# Sheet1.net
KiCad netlist of a schematic drawn in Altium Designer
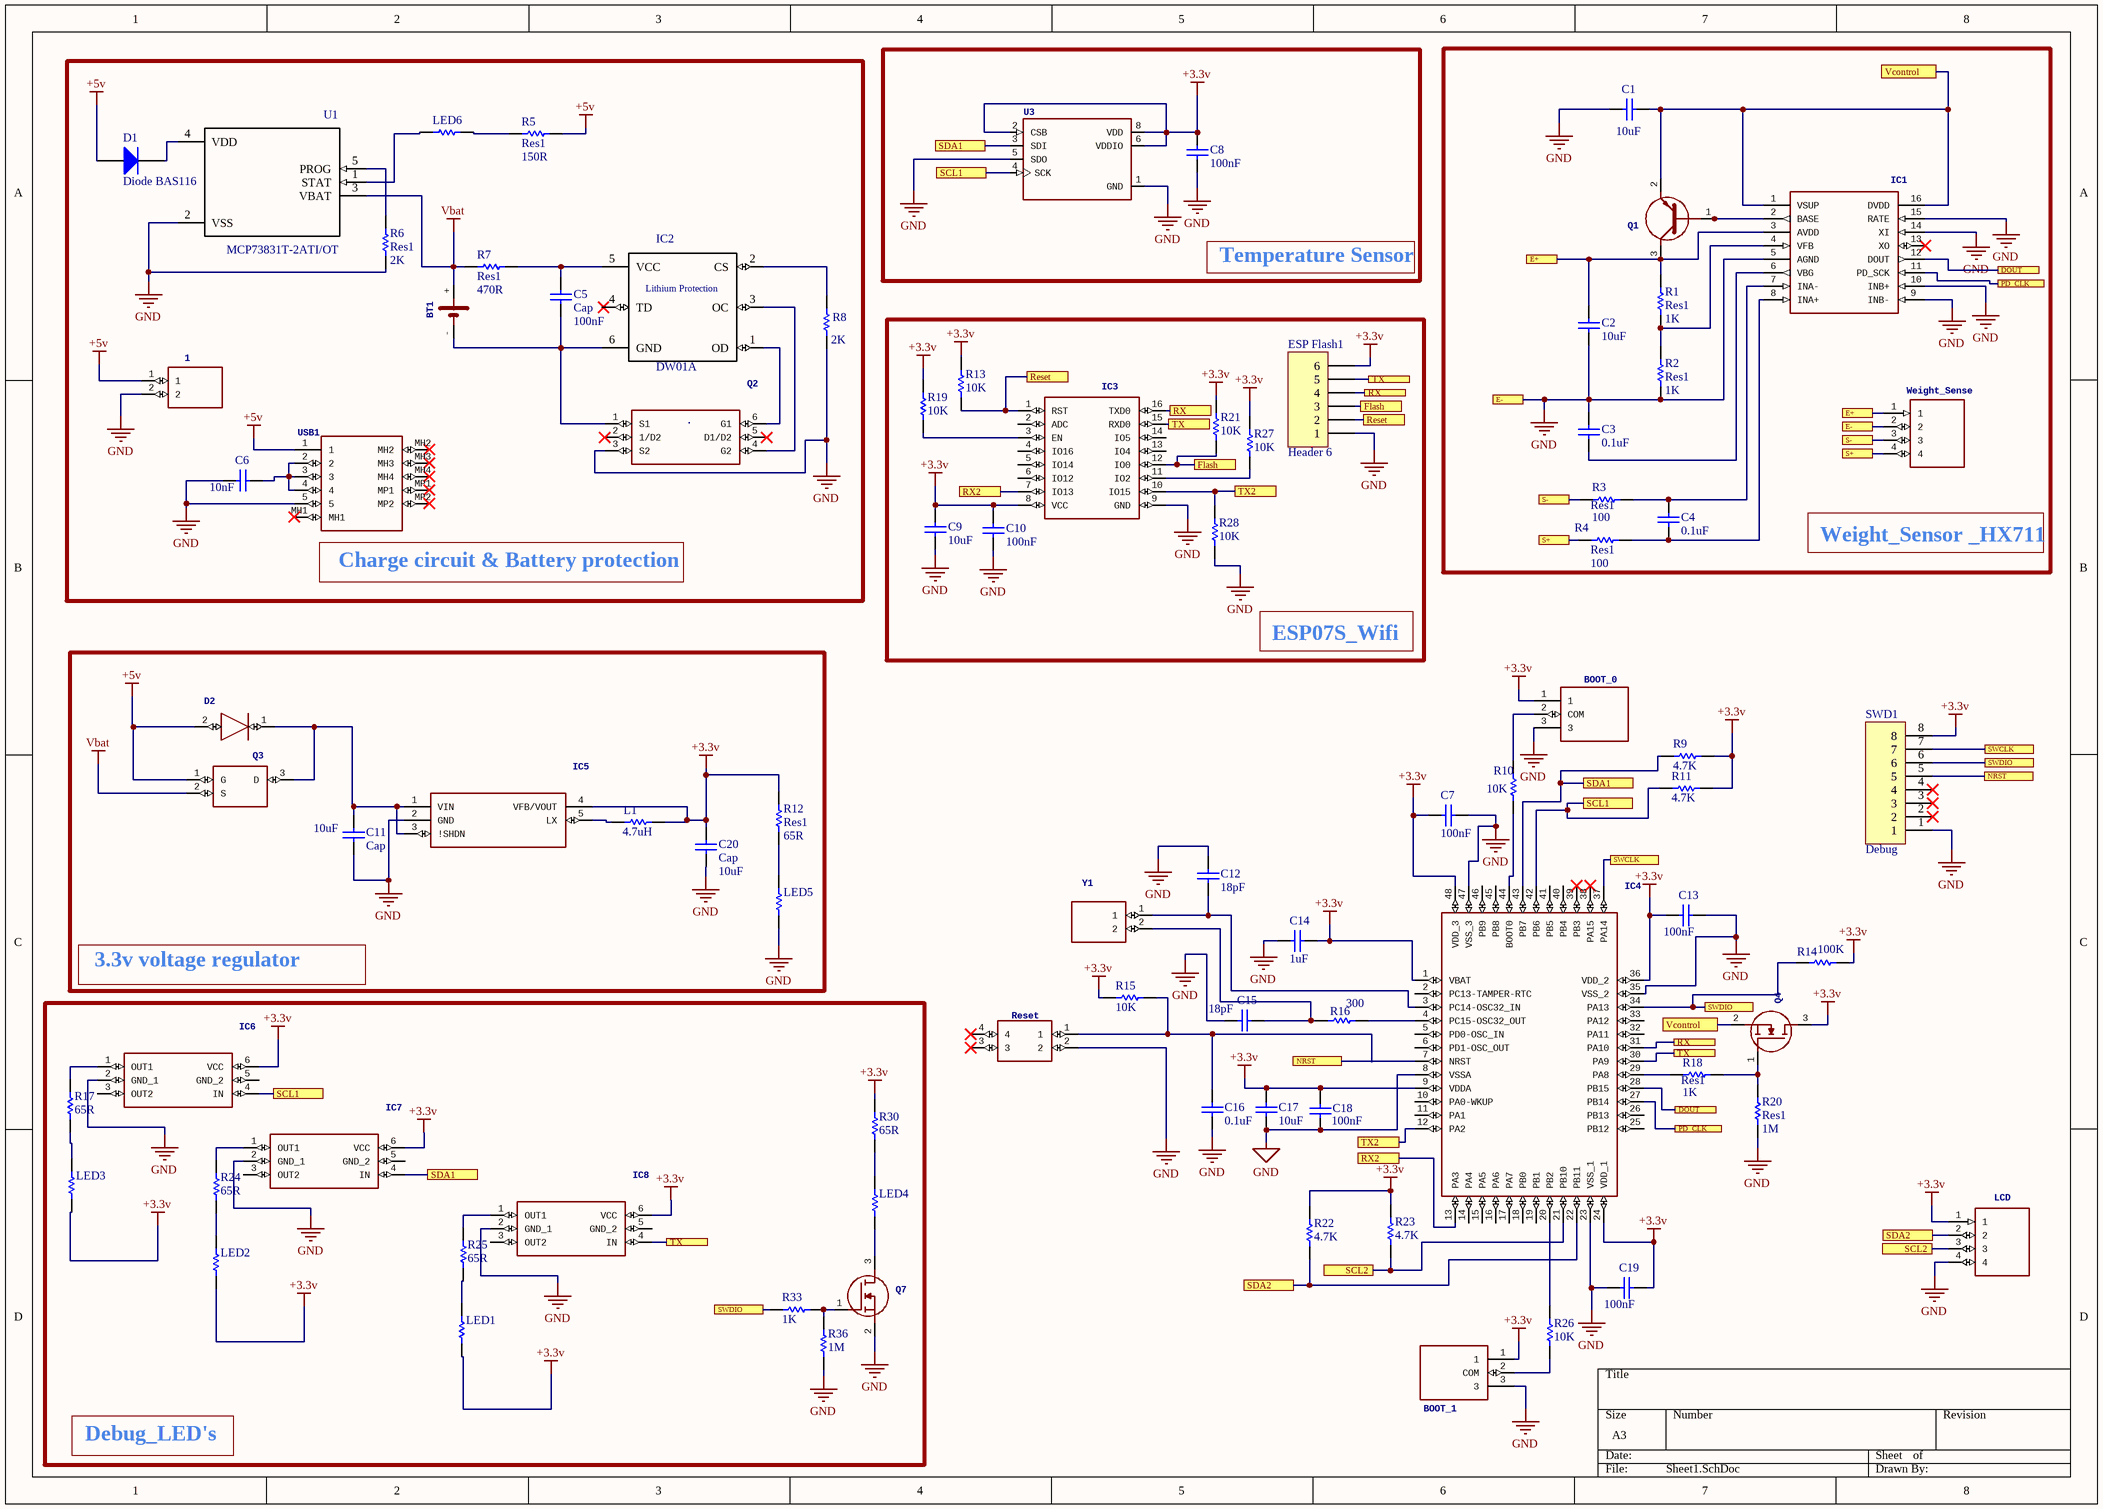
[diagram p0: Sheet1.SchDoc]

(export (version "E")
  (design (tool "Eeschema 10.0.6"))
  (components
    (comp (ref "1")
      (value "P=3.81mm Screw terminal   Source:  Datasheet")
      (footprint "SHDR2W80P0X381_1X2_802X740X880")
      (fields (field (name "MANUFACTURER_PART_NUMBER") "DB125-3.81-2P"))
      (libsource (lib "DB125-3") (part "DB125-3.81-2P"))
    )
    (comp (ref "BOOT_0")
      (value "Slide Switch   Source:  Datasheet")
      (footprint "3PIN_SLIDE_SWITCH")
      (fields
        (field (name "MANUFACTURER_PART_NUMBER") "EG1218")
        (field (name "MOUSER_PART_NUMBER") "612-EG1218")
      )
      (libsource (lib "EG1218") (part "EG1218"))
    )
    (comp (ref "BOOT_1")
      (value "Slide Switch   Source:  Datasheet")
      (footprint "3PIN_SLIDE_SWITCH")
      (fields
        (field (name "MANUFACTURER_PART_NUMBER") "EG1218")
        (field (name "MOUSER_PART_NUMBER") "612-EG1218")
      )
      (libsource (lib "EG1218") (part "EG1218"))
    )
    (comp (ref "BT1")
      (value "Lithium-Ion Battery Holder, 1 Cell, Plastic UL 94V-O, SMT Check prices")
      (footprint "BAT_1042")
      (fields (field (name "MF") "Keystone Electronics Corp.") (field (name "MP") "1042"))
      (libsource (lib "1042") (part "1042"))
    )
    (comp (ref "C1")
      (value "10uF")
      (footprint "C1206")
      (description "Capacitor (Semiconductor SIM Model)")
      (fields (field (name "Comment") "Cap Semi") (field (name "PUBLISHER") "Altium Limited"))
      (libsource (lib "Miscellaneous Devices") (part "Cap Semi"))
    )
    (comp (ref "C2")
      (value "10uF")
      (footprint "C1206")
      (description "Capacitor (Semiconductor SIM Model)")
      (fields (field (name "Comment") "Cap Semi") (field (name "PUBLISHER") "Altium Limited"))
      (libsource (lib "Miscellaneous Devices") (part "Cap Semi"))
    )
    (comp (ref "C3")
      (value "0.1uF")
      (footprint "C1206")
      (description "Capacitor (Semiconductor SIM Model)")
      (fields (field (name "Comment") "Cap Semi") (field (name "PUBLISHER") "Altium Limited"))
      (libsource (lib "Miscellaneous Devices") (part "Cap Semi"))
    )
    (comp (ref "C4")
      (value "0.1uF")
      (footprint "C1206")
      (description "Capacitor (Semiconductor SIM Model)")
      (fields (field (name "Comment") "Cap Semi") (field (name "PUBLISHER") "Altium Limited"))
      (libsource (lib "Miscellaneous Devices") (part "Cap Semi"))
    )
    (comp (ref "C5")
      (value "Cap")
      (footprint "C1206")
      (description "Capacitor")
      (fields (field (name "ALTIUM_VALUE") "100nF") (field (name "PUBLISHER") "Altium Limited"))
      (libsource (lib "Miscellaneous Devices") (part "Cap"))
    )
    (comp (ref "C6")
      (value "10nF")
      (footprint "C1206")
      (description "Capacitor")
      (fields (field (name "PUBLISHER") "Altium Limited"))
      (libsource (lib "Miscellaneous Devices") (part "Cap"))
    )
    (comp (ref "C7")
      (value "100nF")
      (footprint "C1206")
      (description "Capacitor")
      (fields (field (name "PUBLISHER") "Altium Limited"))
      (libsource (lib "Miscellaneous Devices") (part "Cap"))
    )
    (comp (ref "C8")
      (value "100nF")
      (footprint "C1206")
      (description "Capacitor")
      (fields (field (name "PUBLISHER") "Altium Limited"))
      (libsource (lib "Miscellaneous Devices") (part "Cap"))
    )
    (comp (ref "C9")
      (value "10uF")
      (footprint "C1206")
      (description "Capacitor")
      (fields (field (name "PUBLISHER") "Altium Limited"))
      (libsource (lib "Miscellaneous Devices") (part "Cap"))
    )
    (comp (ref "C10")
      (value "100nF")
      (footprint "C1206")
      (description "Capacitor")
      (fields (field (name "PUBLISHER") "Altium Limited"))
      (libsource (lib "Miscellaneous Devices") (part "Cap"))
    )
    (comp (ref "C11")
      (value "Cap")
      (footprint "C1206")
      (description "Capacitor")
      (fields (field (name "ALTIUM_VALUE") "10uF") (field (name "PUBLISHER") "Altium Limited"))
      (libsource (lib "Miscellaneous Devices") (part "Cap"))
    )
    (comp (ref "C12")
      (value "18pF")
      (footprint "C1206")
      (description "Capacitor")
      (fields (field (name "PUBLISHER") "Altium Limited"))
      (libsource (lib "Miscellaneous Devices") (part "Cap"))
    )
    (comp (ref "C13")
      (value "100nF")
      (footprint "C1206")
      (description "Capacitor")
      (fields (field (name "PUBLISHER") "Altium Limited"))
      (libsource (lib "Miscellaneous Devices") (part "Cap"))
    )
    (comp (ref "C14")
      (value "1uF")
      (footprint "C1206")
      (description "Capacitor")
      (fields (field (name "PUBLISHER") "Altium Limited"))
      (libsource (lib "Miscellaneous Devices") (part "Cap"))
    )
    (comp (ref "C15")
      (value "18pF")
      (footprint "C1206")
      (description "Capacitor")
      (fields (field (name "PUBLISHER") "Altium Limited"))
      (libsource (lib "Miscellaneous Devices") (part "Cap"))
    )
    (comp (ref "C16")
      (value "0.1uF")
      (footprint "C1206")
      (description "Capacitor")
      (fields (field (name "PUBLISHER") "Altium Limited"))
      (libsource (lib "Miscellaneous Devices") (part "Cap"))
    )
    (comp (ref "C17")
      (value "10uF")
      (footprint "C1206")
      (description "Capacitor")
      (fields (field (name "PUBLISHER") "Altium Limited"))
      (libsource (lib "Miscellaneous Devices") (part "Cap"))
    )
    (comp (ref "C18")
      (value "100nF")
      (footprint "C1206")
      (description "Capacitor")
      (fields (field (name "PUBLISHER") "Altium Limited"))
      (libsource (lib "Miscellaneous Devices") (part "Cap"))
    )
    (comp (ref "C19")
      (value "100nF")
      (footprint "C1206")
      (description "Capacitor")
      (fields (field (name "PUBLISHER") "Altium Limited"))
      (libsource (lib "Miscellaneous Devices") (part "Cap"))
    )
    (comp (ref "C20")
      (value "Cap")
      (footprint "C1206")
      (description "Capacitor")
      (fields (field (name "ALTIUM_VALUE") "10uF") (field (name "PUBLISHER") "Altium Limited"))
      (libsource (lib "Miscellaneous Devices") (part "Cap"))
    )
    (comp (ref "D1")
      (value "Diode BAS116")
      (footprint "SOT-23_N")
      (description "Silicon Low Leakage Diode")
      (fields (field (name "PUBLISHER") "Altium Limited"))
      (libsource (lib "Miscellaneous Devices") (part "Diode BAS116"))
    )
    (comp (ref "D2")
      (value "Diode, NXP, PMEG3010ER NXP PMEG3010ER, SMT Schottky Diode, 30V 1A, 2-Pin SOD-123   Source:  Datasheet")
      (footprint "SODFL3517X110N")
      (fields (field (name "MANUFACTURER_PART_NUMBER") "PMEG3010ER"))
      (libsource (lib "PMEG3010ER") (part "PMEG3010ER"))
    )
    (comp (ref "ESP Flash1")
      (value "Header 6")
      (footprint "HDR1X6")
      (description "Header, 6-Pin")
      (fields (field (name "PUBLISHER") "Altium Limited"))
      (libsource (lib "Miscellaneous Connectors") (part "Header 6"))
    )
    (comp (ref "IC1")
      (value "24-Bit Analog-to-Digital Converter (ADC) for Weigh Scales   Source:  Datasheet")
      (footprint "SOIC127P600X160-16N")
      (fields (field (name "MANUFACTURER_PART_NUMBER") "HX711"))
      (libsource (lib "HX711") (part "HX711"))
    )
    (comp (ref "IC2")
      (value "DW01A")
      (footprint "*SOT23-6")
      (description "One Cell Lithium-ion/Polymer Battery Protection IC")
      (fields (field (name "MF") "Fortune Semiconductor"))
      (libsource (lib "DW01A") (part "DW01A"))
    )
    (comp (ref "IC3")
      (value "RF SOLUTIONS - ESP-12S - WIFI MODULE, 2.484GHZ, 9 I/O PORT   Source:  Datasheet")
      (footprint "ESP12S")
      (fields
        (field (name "MANUFACTURER_PART_NUMBER") "ESP-12S")
        (field (name "MOUSER_PART_NUMBER") "223-ESP-12S")
        (field (name "RS_PART_NUMBER") "1697593")
      )
      (libsource (lib "ESP-12S") (part "ESP-12S"))
    )
    (comp (ref "IC4")
      (value "STM32F103C8T6, 32 bit ARM Cortex M3 Microcontroller 72MHz 64kb Flash, 20kb RAM, USB I2C SPI 48-Pin LQFP   Source:  Datasheet")
      (footprint "QFP50P900X900X160-48N")
      (fields
        (field (name "MANUFACTURER_PART_NUMBER") "STM32F103C8T6")
        (field (name "MOUSER_PART_NUMBER") "511-STM32F103C8T6")
      )
      (libsource (lib "STM32F103C8T6") (part "STM32F103C8T6"))
    )
    (comp (ref "IC5")
      (value "Sw. Reg. PWM/PFM 2MHz 500mA 3.3V TSOT5   Source:  Datasheet")
      (footprint "SOT95P280X110-5N")
      (fields
        (field (name "MANUFACTURER_PART_NUMBER") "MCP1603T-330I/OS")
        (field (name "MOUSER_PART_NUMBER") "579-MCP1603T-330I/OS")
        (field (name "RS_PART_NUMBER") "7386235P")
      )
      (libsource (lib "MCP1603T-330I_OS") (part "MCP1603T-330I_OS"))
    )
    (comp (ref "IC6")
      (value "MAXIM INTEGRATED PRODUCTS - MAX2472EUT+T - VIDEO BUFFER AMP, SOT-23-6   Source:  Datasheet")
      (footprint "SOT95P280X145-6N")
      (fields
        (field (name "MANUFACTURER_PART_NUMBER") "MAX2472EUT+T")
        (field (name "MOUSER_PART_NUMBER") "700-MAX2472EUTT")
      )
      (libsource (lib "MAX2472EUT+T") (part "MAX2472EUT+T"))
    )
    (comp (ref "IC7")
      (value "MAXIM INTEGRATED PRODUCTS - MAX2472EUT+T - VIDEO BUFFER AMP, SOT-23-6   Source:  Datasheet")
      (footprint "SOT95P280X145-6N")
      (fields
        (field (name "MANUFACTURER_PART_NUMBER") "MAX2472EUT+T")
        (field (name "MOUSER_PART_NUMBER") "700-MAX2472EUTT")
      )
      (libsource (lib "MAX2472EUT+T") (part "MAX2472EUT+T"))
    )
    (comp (ref "IC8")
      (value "MAXIM INTEGRATED PRODUCTS - MAX2472EUT+T - VIDEO BUFFER AMP, SOT-23-6   Source:  Datasheet")
      (footprint "SOT95P280X145-6N")
      (fields
        (field (name "MANUFACTURER_PART_NUMBER") "MAX2472EUT+T")
        (field (name "MOUSER_PART_NUMBER") "700-MAX2472EUTT")
      )
      (libsource (lib "MAX2472EUT+T") (part "MAX2472EUT+T"))
    )
    (comp (ref "L1")
      (value "4.7uH")
      (footprint "Miscellaneous Devices:C1206")
      (description "Resistor")
      (fields (field (name "PUBLISHER") "Altium Limited"))
      (libsource (lib "Miscellaneous Devices") (part "Res1"))
    )
    (comp (ref "LCD")
      (value "European P.C.B. type terminal blocks  EK series 4 pole   Source:  Datasheet")
      (footprint "SHDR4W90P0X381_1X4_1524X740X85")
      (fields (field (name "MANUFACTURER_PART_NUMBER") "EK381V-04P"))
      (libsource (lib "EK381V-04P") (part "EK381V-04P"))
    )
    (comp (ref "LED1")
      (value "~")
      (footprint "Miscellaneous Devices:C1206")
      (description "Resistor")
      (fields (field (name "PUBLISHER") "Altium Limited"))
      (libsource (lib "Miscellaneous Devices") (part "Res1"))
    )
    (comp (ref "LED2")
      (value "~")
      (footprint "Miscellaneous Devices:C1206")
      (description "Resistor")
      (fields (field (name "PUBLISHER") "Altium Limited"))
      (libsource (lib "Miscellaneous Devices") (part "Res1"))
    )
    (comp (ref "LED3")
      (value "~")
      (footprint "Miscellaneous Devices:C1206")
      (description "Resistor")
      (fields (field (name "PUBLISHER") "Altium Limited"))
      (libsource (lib "Miscellaneous Devices") (part "Res1"))
    )
    (comp (ref "LED4")
      (value "~")
      (footprint "Miscellaneous Devices:C1206")
      (description "Resistor")
      (fields (field (name "PUBLISHER") "Altium Limited"))
      (libsource (lib "Miscellaneous Devices") (part "Res1"))
    )
    (comp (ref "LED5")
      (value "~")
      (footprint "Miscellaneous Devices:C1206")
      (description "Resistor")
      (fields (field (name "PUBLISHER") "Altium Limited"))
      (libsource (lib "Miscellaneous Devices") (part "Res1"))
    )
    (comp (ref "LED6")
      (value "~")
      (footprint "Miscellaneous Devices:C1206")
      (description "Resistor")
      (fields (field (name "PUBLISHER") "Altium Limited"))
      (libsource (lib "Miscellaneous Devices") (part "Res1"))
    )
    (comp (ref "Q1")
      (value "Silicon Epitaxial Planar Transistor, PNP   Source:  Datasheet")
      (footprint "SOT95P240X110-3N")
      (fields (field (name "MANUFACTURER_PART_NUMBER") "S8550"))
      (libsource (lib "S8550") (part "S8550"))
    )
    (comp (ref "Q2")
      (value "Dual N-Channel Enhancement Mode MOSFET   Source:  Datasheet")
      (footprint "UMW8205A:SOT95P285X140-6N")
      (fields (field (name "MANUFACTURER_PART_NUMBER") "UMW8205A"))
      (libsource (lib "UMW8205A") (part "UMW8205A"))
    )
    (comp (ref "Q3")
      (value "INFINEON - IRLML6401TRPBF - MOSFET, P, MICRO3   Source:  Datasheet")
      (footprint "SOT95P237X112-3N")
      (fields
        (field (name "MANUFACTURER_PART_NUMBER") "IRLML6401TRPBF")
        (field (name "MOUSER_PART_NUMBER") "942-IRLML6401TRPBF")
        (field (name "RS_PART_NUMBER") "0301316P")
      )
      (libsource (lib "IRLML6401TRPBF") (part "IRLML6401TRPBF"))
    )
    (comp (ref "Q4")
      (value "360 mA, 60 V, N-CHANNEL, Si, SMALL SIGNAL, MOSFET, TO-236AB   Source:  Datasheet")
      (footprint "SOT95P230X110-3N")
      (fields (field (name "MANUFACTURER_PART_NUMBER") "BSS138BK"))
      (libsource (lib "BSS138BK") (part "BSS138BK"))
    )
    (comp (ref "Q7")
      (value "360 mA, 60 V, N-CHANNEL, Si, SMALL SIGNAL, MOSFET, TO-236AB   Source:  Datasheet")
      (footprint "SOT95P230X110-3N")
      (fields (field (name "MANUFACTURER_PART_NUMBER") "BSS138BK"))
      (libsource (lib "BSS138BK") (part "BSS138BK"))
    )
    (comp (ref "R1")
      (value "Res1")
      (footprint "C1206")
      (description "Resistor")
      (fields (field (name "ALTIUM_VALUE") "1K") (field (name "PUBLISHER") "Altium Limited"))
      (libsource (lib "Miscellaneous Devices") (part "Res1"))
    )
    (comp (ref "R2")
      (value "Res1")
      (footprint "C1206")
      (description "Resistor")
      (fields (field (name "ALTIUM_VALUE") "1K") (field (name "PUBLISHER") "Altium Limited"))
      (libsource (lib "Miscellaneous Devices") (part "Res1"))
    )
    (comp (ref "R3")
      (value "Res1")
      (footprint "C1206")
      (description "Resistor")
      (fields (field (name "ALTIUM_VALUE") "100") (field (name "PUBLISHER") "Altium Limited"))
      (libsource (lib "Miscellaneous Devices") (part "Res1"))
    )
    (comp (ref "R4")
      (value "Res1")
      (footprint "C1206")
      (description "Resistor")
      (fields (field (name "ALTIUM_VALUE") "100") (field (name "PUBLISHER") "Altium Limited"))
      (libsource (lib "Miscellaneous Devices") (part "Res1"))
    )
    (comp (ref "R5")
      (value "Res1")
      (footprint "Miscellaneous Devices:C1206")
      (description "Resistor")
      (fields (field (name "ALTIUM_VALUE") "150R") (field (name "PUBLISHER") "Altium Limited"))
      (libsource (lib "Miscellaneous Devices") (part "Res1"))
    )
    (comp (ref "R6")
      (value "Res1")
      (footprint "Miscellaneous Devices:C1206")
      (description "Resistor")
      (fields (field (name "ALTIUM_VALUE") "2K") (field (name "PUBLISHER") "Altium Limited"))
      (libsource (lib "Miscellaneous Devices") (part "Res1"))
    )
    (comp (ref "R7")
      (value "Res1")
      (footprint "Miscellaneous Devices:C1206")
      (description "Resistor")
      (fields (field (name "ALTIUM_VALUE") "470R") (field (name "PUBLISHER") "Altium Limited"))
      (libsource (lib "Miscellaneous Devices") (part "Res1"))
    )
    (comp (ref "R8")
      (value "2K")
      (footprint "Miscellaneous Devices:C1206")
      (description "Resistor")
      (fields (field (name "PUBLISHER") "Altium Limited"))
      (libsource (lib "Miscellaneous Devices") (part "Res1"))
    )
    (comp (ref "R9")
      (value "4.7K")
      (footprint "Miscellaneous Devices:C1206")
      (description "Resistor")
      (fields (field (name "PUBLISHER") "Altium Limited"))
      (libsource (lib "Miscellaneous Devices") (part "Res1"))
    )
    (comp (ref "R10")
      (value "10K")
      (footprint "Miscellaneous Devices:C1206")
      (description "Resistor")
      (fields (field (name "PUBLISHER") "Altium Limited"))
      (libsource (lib "Miscellaneous Devices") (part "Res1"))
    )
    (comp (ref "R11")
      (value "4.7K")
      (footprint "Miscellaneous Devices:C1206")
      (description "Resistor")
      (fields (field (name "PUBLISHER") "Altium Limited"))
      (libsource (lib "Miscellaneous Devices") (part "Res1"))
    )
    (comp (ref "R12")
      (value "Res1")
      (footprint "Miscellaneous Devices:C1206")
      (description "Resistor")
      (fields (field (name "ALTIUM_VALUE") "65R") (field (name "PUBLISHER") "Altium Limited"))
      (libsource (lib "Miscellaneous Devices") (part "Res1"))
    )
    (comp (ref "R13")
      (value "10K")
      (footprint "Miscellaneous Devices:C1206")
      (description "Resistor")
      (fields (field (name "PUBLISHER") "Altium Limited"))
      (libsource (lib "Miscellaneous Devices") (part "Res1"))
    )
    (comp (ref "R14")
      (value "100K")
      (footprint "Miscellaneous Devices:C1206")
      (description "Resistor")
      (fields (field (name "PUBLISHER") "Altium Limited"))
      (libsource (lib "Miscellaneous Devices") (part "Res1"))
    )
    (comp (ref "R15")
      (value "10K")
      (footprint "Miscellaneous Devices:C1206")
      (description "Resistor")
      (fields (field (name "PUBLISHER") "Altium Limited"))
      (libsource (lib "Miscellaneous Devices") (part "Res1"))
    )
    (comp (ref "R16")
      (value "300")
      (footprint "Miscellaneous Devices:C1206")
      (description "Resistor")
      (fields (field (name "PUBLISHER") "Altium Limited"))
      (libsource (lib "Miscellaneous Devices") (part "Res1"))
    )
    (comp (ref "R17")
      (value "65R")
      (footprint "Miscellaneous Devices:C1206")
      (description "Resistor")
      (fields (field (name "PUBLISHER") "Altium Limited"))
      (libsource (lib "Miscellaneous Devices") (part "Res1"))
    )
    (comp (ref "R18")
      (value "Res1")
      (footprint "C1206")
      (description "Resistor")
      (fields (field (name "ALTIUM_VALUE") "1K") (field (name "PUBLISHER") "Altium Limited"))
      (libsource (lib "Miscellaneous Devices") (part "Res1"))
    )
    (comp (ref "R19")
      (value "10K")
      (footprint "Miscellaneous Devices:C1206")
      (description "Resistor")
      (fields (field (name "PUBLISHER") "Altium Limited"))
      (libsource (lib "Miscellaneous Devices") (part "Res1"))
    )
    (comp (ref "R20")
      (value "Res1")
      (footprint "C1206")
      (description "Resistor")
      (fields (field (name "ALTIUM_VALUE") "1M") (field (name "PUBLISHER") "Altium Limited"))
      (libsource (lib "Miscellaneous Devices") (part "Res1"))
    )
    (comp (ref "R21")
      (value "10K")
      (footprint "Miscellaneous Devices:C1206")
      (description "Resistor")
      (fields (field (name "PUBLISHER") "Altium Limited"))
      (libsource (lib "Miscellaneous Devices") (part "Res1"))
    )
    (comp (ref "R22")
      (value "4.7K")
      (footprint "Miscellaneous Devices:C1206")
      (description "Resistor")
      (fields (field (name "PUBLISHER") "Altium Limited"))
      (libsource (lib "Miscellaneous Devices") (part "Res1"))
    )
    (comp (ref "R23")
      (value "4.7K")
      (footprint "Miscellaneous Devices:C1206")
      (description "Resistor")
      (fields (field (name "PUBLISHER") "Altium Limited"))
      (libsource (lib "Miscellaneous Devices") (part "Res1"))
    )
    (comp (ref "R24")
      (value "65R")
      (footprint "Miscellaneous Devices:C1206")
      (description "Resistor")
      (fields (field (name "PUBLISHER") "Altium Limited"))
      (libsource (lib "Miscellaneous Devices") (part "Res1"))
    )
    (comp (ref "R25")
      (value "65R")
      (footprint "Miscellaneous Devices:C1206")
      (description "Resistor")
      (fields (field (name "PUBLISHER") "Altium Limited"))
      (libsource (lib "Miscellaneous Devices") (part "Res1"))
    )
    (comp (ref "R26")
      (value "10K")
      (footprint "Miscellaneous Devices:C1206")
      (description "Resistor")
      (fields (field (name "PUBLISHER") "Altium Limited"))
      (libsource (lib "Miscellaneous Devices") (part "Res1"))
    )
    (comp (ref "R27")
      (value "10K")
      (footprint "Miscellaneous Devices:C1206")
      (description "Resistor")
      (fields (field (name "PUBLISHER") "Altium Limited"))
      (libsource (lib "Miscellaneous Devices") (part "Res1"))
    )
    (comp (ref "R28")
      (value "10K")
      (footprint "Miscellaneous Devices:C1206")
      (description "Resistor")
      (fields (field (name "PUBLISHER") "Altium Limited"))
      (libsource (lib "Miscellaneous Devices") (part "Res1"))
    )
    (comp (ref "R30")
      (value "65R")
      (footprint "Miscellaneous Devices:C1206")
      (description "Resistor")
      (fields (field (name "PUBLISHER") "Altium Limited"))
      (libsource (lib "Miscellaneous Devices") (part "Res1"))
    )
    (comp (ref "R33")
      (value "1K")
      (footprint "Miscellaneous Devices:C1206")
      (description "Resistor")
      (fields (field (name "PUBLISHER") "Altium Limited"))
      (libsource (lib "Miscellaneous Devices") (part "Res1"))
    )
    (comp (ref "R36")
      (value "1M")
      (footprint "Miscellaneous Devices:C1206")
      (description "Resistor")
      (fields (field (name "PUBLISHER") "Altium Limited"))
      (libsource (lib "Miscellaneous Devices") (part "Res1"))
    )
    (comp (ref "Reset")
      (value "IP67 Button Tactile Switch, SPST 50 mA 3.5mm Surface Mount   Source:  Datasheet")
      (footprint "KSC401G50SHLFS")
      (fields
        (field (name "MANUFACTURER_PART_NUMBER") "KSC222GLFS")
        (field (name "MOUSER_PART_NUMBER") "611-KSC222GLFS")
        (field (name "RS_PART_NUMBER") "8998582")
      )
      (libsource (lib "KSC222GLFS") (part "KSC222GLFS"))
    )
    (comp (ref "SWD1")
      (value "Debug")
      (footprint "HDR1X8")
      (description "Header, 8-Pin")
      (fields (field (name "PUBLISHER") "Altium Limited"))
      (libsource (lib "Miscellaneous Connectors") (part "Header 8"))
    )
    (comp (ref "U1")
      (value "MCP73831T-2ATI/OT")
      (footprint "MCP73831T-2ATI_OT:*SOT95P280X145-5N")
      (description "MCP73831 Series Li-Ion/Li-Pol 15 mA - 500 mA 4.2 V Charge Controller - SOT-23-5")
      (fields (field (name "MF") "Microchip"))
      (libsource (lib "Miscellaneous Devices") (part "MCP73831T-2ATI/OT"))
    )
    (comp (ref "U3")
      (value "BMP280 Absolute Barometric Pressure Sensor for Battery Powered Devices 2 x 2.5mm Check prices")
      (footprint "BMP280:XDCR_BMP280")
      (fields (field (name "MF") "Bosch") (field (name "MP") "BMP280"))
      (libsource (lib "BMP280") (part "BMP280"))
    )
    (comp (ref "USB1")
      (value "USB Connectors 5P RoHS   Source:  Datasheet")
      (footprint "C40943")
      (fields (field (name "MANUFACTURER_PART_NUMBER") "C40943"))
      (libsource (lib "C40943") (part "C40943"))
    )
    (comp (ref "Weight_Sense")
      (value "European P.C.B. type terminal blocks  EK series 4 pole   Source:  Datasheet")
      (footprint "SHDR4W90P0X381_1X4_1524X740X85")
      (fields (field (name "MANUFACTURER_PART_NUMBER") "EK381V-04P"))
      (libsource (lib "EK381V-04P") (part "EK381V-04P"))
    )
    (comp (ref "Y1")
      (value "Automotive use crystal unit, 2-pin, NX5032GA   Source:  Datasheet")
      (footprint "NX5032GA")
      (fields
        (field (name "MANUFACTURER_PART_NUMBER") "NX5032GA-8.000M-STD-CSU-1")
        (field (name "MOUSER_PART_NUMBER") "344-NX5032GA8MCSU1")
        (field (name "RS_PART_NUMBER") "1847981")
      )
      (libsource (lib "NX5032GA-8") (part "NX5032GA-8.000M-STD-CSU-1"))
    )
  )
  (nets
    (net (code "1") (name "+3.3v") (class "Default")
      (node (ref "BOOT_0") (pin "1") (pinfunction "1_1") (pintype "power_in"))
      (node (ref "BOOT_1") (pin "1") (pinfunction "1_1") (pintype "power_in"))
      (node (ref "C10") (pin "2") (pinfunction "2_2") (pintype "passive"))
      (node (ref "C13") (pin "1") (pinfunction "1_1") (pintype "passive"))
      (node (ref "C14") (pin "1") (pinfunction "1_1") (pintype "passive"))
      (node (ref "C17") (pin "1") (pinfunction "1_1") (pintype "passive"))
      (node (ref "C18") (pin "2") (pinfunction "2_2") (pintype "passive"))
      (node (ref "C19") (pin "2") (pinfunction "2_2") (pintype "passive"))
      (node (ref "C20") (pin "2") (pinfunction "2_2") (pintype "passive"))
      (node (ref "C7") (pin "1") (pinfunction "1_1") (pintype "passive"))
      (node (ref "C8") (pin "2") (pinfunction "2_2") (pintype "passive"))
      (node (ref "C9") (pin "2") (pinfunction "2_2") (pintype "passive"))
      (node (ref "ESP Flash1") (pin "6") (pinfunction "6_6") (pintype "passive"))
      (node (ref "IC3") (pin "8") (pinfunction "VCC_8") (pintype "bidirectional"))
      (node (ref "IC4") (pin "1") (pinfunction "VBAT_1") (pintype "bidirectional"))
      (node (ref "IC4") (pin "24") (pinfunction "VDD_1_24") (pintype "bidirectional"))
      (node (ref "IC4") (pin "36") (pinfunction "VDD_2_36") (pintype "bidirectional"))
      (node (ref "IC4") (pin "48") (pinfunction "VDD_3_48") (pintype "bidirectional"))
      (node (ref "IC4") (pin "9") (pinfunction "VDDA_9") (pintype "bidirectional"))
      (node (ref "IC5") (pin "4") (pinfunction "VFB/VOUT_4") (pintype "power_in"))
      (node (ref "IC6") (pin "6") (pinfunction "VCC_6") (pintype "bidirectional"))
      (node (ref "IC7") (pin "6") (pinfunction "VCC_6") (pintype "bidirectional"))
      (node (ref "IC8") (pin "6") (pinfunction "VCC_6") (pintype "bidirectional"))
      (node (ref "L1") (pin "1") (pinfunction "1_1") (pintype "passive"))
      (node (ref "LCD") (pin "1") (pinfunction "1_1") (pintype "input"))
      (node (ref "LED1") (pin "2") (pinfunction "2_2") (pintype "passive"))
      (node (ref "LED2") (pin "2") (pinfunction "2_2") (pintype "passive"))
      (node (ref "LED3") (pin "2") (pinfunction "2_2") (pintype "passive"))
      (node (ref "Q4") (pin "3") (pinfunction "D_3") (pintype "bidirectional"))
      (node (ref "R11") (pin "1") (pinfunction "1_1") (pintype "passive"))
      (node (ref "R12") (pin "1") (pinfunction "1_1") (pintype "passive"))
      (node (ref "R13") (pin "1") (pinfunction "1_1") (pintype "passive"))
      (node (ref "R14") (pin "1") (pinfunction "1_1") (pintype "passive"))
      (node (ref "R15") (pin "2") (pinfunction "2_2") (pintype "passive"))
      (node (ref "R19") (pin "1") (pinfunction "1_1") (pintype "passive"))
      (node (ref "R21") (pin "1") (pinfunction "1_1") (pintype "passive"))
      (node (ref "R22") (pin "1") (pinfunction "1_1") (pintype "passive"))
      (node (ref "R23") (pin "1") (pinfunction "1_1") (pintype "passive"))
      (node (ref "R27") (pin "1") (pinfunction "1_1") (pintype "passive"))
      (node (ref "R30") (pin "1") (pinfunction "1_1") (pintype "passive"))
      (node (ref "R9") (pin "1") (pinfunction "1_1") (pintype "passive"))
      (node (ref "SWD1") (pin "8") (pinfunction "8_8") (pintype "power_in"))
      (node (ref "U3") (pin "2") (pinfunction "CSB_2") (pintype "input"))
      (node (ref "U3") (pin "6") (pinfunction "VDDIO_6") (pintype "power_in"))
      (node (ref "U3") (pin "8") (pinfunction "VDD_8") (pintype "power_in"))
    )
    (net (code "2") (name "+5v") (class "Default")
      (node (ref "1") (pin "1") (pinfunction "1_1") (pintype "bidirectional"))
      (node (ref "D1") (pin "1") (pinfunction "A_1") (pintype "passive"))
      (node (ref "D2") (pin "2") (pinfunction "A_2") (pintype "bidirectional"))
      (node (ref "Q3") (pin "1") (pinfunction "G_1") (pintype "bidirectional"))
      (node (ref "R5") (pin "1") (pinfunction "1_1") (pintype "passive"))
      (node (ref "USB1") (pin "1") (pinfunction "1_1") (pintype "power_in"))
    )
    (net (code "3") (name "/DOUT") (class "Default")
      (node (ref "IC1") (pin "12") (pinfunction "DOUT_12") (pintype "output"))
      (node (ref "IC4") (pin "28") (pinfunction "PB15_28") (pintype "bidirectional"))
    )
    (net (code "4") (name "/E+") (class "Default")
      (node (ref "C2") (pin "2") (pinfunction "2_2") (pintype "passive"))
      (node (ref "IC1") (pin "3") (pinfunction "AVDD_3") (pintype "power_in"))
      (node (ref "Q1") (pin "3") (pinfunction "C_3") (pintype "bidirectional"))
      (node (ref "R1") (pin "2") (pinfunction "2_2") (pintype "passive"))
      (node (ref "Weight_Sense") (pin "1") (pinfunction "1_1") (pintype "input"))
    )
    (net (code "5") (name "/Flash") (class "Default")
      (node (ref "ESP Flash1") (pin "3") (pinfunction "3_3") (pintype "passive"))
      (node (ref "IC3") (pin "12") (pinfunction "IO0_12") (pintype "bidirectional"))
      (node (ref "R21") (pin "2") (pinfunction "2_2") (pintype "passive"))
    )
    (net (code "6") (name "/NRST") (class "Default")
      (node (ref "IC4") (pin "7") (pinfunction "NRST_7") (pintype "bidirectional"))
      (node (ref "SWD1") (pin "5") (pinfunction "5_5") (pintype "passive"))
    )
    (net (code "7") (name "/PD_CLK") (class "Default")
      (node (ref "IC1") (pin "11") (pinfunction "PD_SCK_11") (pintype "input"))
      (node (ref "IC4") (pin "27") (pinfunction "PB14_27") (pintype "bidirectional"))
    )
    (net (code "8") (name "/RX") (class "Default")
      (node (ref "ESP Flash1") (pin "4") (pinfunction "4_4") (pintype "passive"))
      (node (ref "IC3") (pin "16") (pinfunction "TXD0_16") (pintype "bidirectional"))
      (node (ref "IC4") (pin "31") (pinfunction "PA10_31") (pintype "bidirectional"))
    )
    (net (code "9") (name "/RX2") (class "Default")
      (node (ref "IC3") (pin "7") (pinfunction "IO13_7") (pintype "bidirectional"))
      (node (ref "IC4") (pin "13") (pinfunction "PA3_13") (pintype "bidirectional"))
    )
    (net (code "10") (name "/Reset") (class "Default")
      (node (ref "ESP Flash1") (pin "2") (pinfunction "2_2") (pintype "passive"))
      (node (ref "IC3") (pin "1") (pinfunction "RST_1") (pintype "bidirectional"))
      (node (ref "R13") (pin "2") (pinfunction "2_2") (pintype "passive"))
    )
    (net (code "11") (name "/S+") (class "Default")
      (node (ref "R4") (pin "2") (pinfunction "2_2") (pintype "passive"))
      (node (ref "Weight_Sense") (pin "4") (pinfunction "4_4") (pintype "bidirectional"))
    )
    (net (code "12") (name "/S-") (class "Default")
      (node (ref "R3") (pin "2") (pinfunction "2_2") (pintype "passive"))
      (node (ref "Weight_Sense") (pin "3") (pinfunction "3_3") (pintype "bidirectional"))
    )
    (net (code "13") (name "/SCL1") (class "Default")
      (node (ref "IC4") (pin "42") (pinfunction "PB6_42") (pintype "bidirectional"))
      (node (ref "IC6") (pin "4") (pinfunction "IN_4") (pintype "bidirectional"))
      (node (ref "R11") (pin "2") (pinfunction "2_2") (pintype "passive"))
      (node (ref "U3") (pin "4") (pinfunction "SCK_4") (pintype "input"))
    )
    (net (code "14") (name "/SCL2") (class "Default")
      (node (ref "IC4") (pin "21") (pinfunction "PB10_21") (pintype "bidirectional"))
      (node (ref "LCD") (pin "3") (pinfunction "3_3") (pintype "bidirectional"))
      (node (ref "R23") (pin "2") (pinfunction "2_2") (pintype "passive"))
    )
    (net (code "15") (name "/SDA1") (class "Default")
      (node (ref "IC4") (pin "43") (pinfunction "PB7_43") (pintype "bidirectional"))
      (node (ref "IC7") (pin "4") (pinfunction "IN_4") (pintype "bidirectional"))
      (node (ref "R9") (pin "2") (pinfunction "2_2") (pintype "passive"))
      (node (ref "U3") (pin "3") (pinfunction "SDI_3") (pintype "bidirectional"))
    )
    (net (code "16") (name "/SDA2") (class "Default")
      (node (ref "IC4") (pin "22") (pinfunction "PB11_22") (pintype "bidirectional"))
      (node (ref "LCD") (pin "2") (pinfunction "2_2") (pintype "bidirectional"))
      (node (ref "R22") (pin "2") (pinfunction "2_2") (pintype "passive"))
    )
    (net (code "17") (name "/SWCLK") (class "Default")
      (node (ref "IC4") (pin "37") (pinfunction "PA14_37") (pintype "bidirectional"))
      (node (ref "SWD1") (pin "7") (pinfunction "7_7") (pintype "passive"))
    )
    (net (code "18") (name "/SWDIO") (class "Default")
      (node (ref "IC4") (pin "34") (pinfunction "PA13_34") (pintype "bidirectional"))
      (node (ref "R14") (pin "2") (pinfunction "2_2") (pintype "passive"))
      (node (ref "R33") (pin "2") (pinfunction "2_2") (pintype "passive"))
      (node (ref "SWD1") (pin "6") (pinfunction "6_6") (pintype "passive"))
    )
    (net (code "19") (name "/TX") (class "Default")
      (node (ref "ESP Flash1") (pin "5") (pinfunction "5_5") (pintype "passive"))
      (node (ref "IC3") (pin "15") (pinfunction "RXD0_15") (pintype "bidirectional"))
      (node (ref "IC4") (pin "30") (pinfunction "PA9_30") (pintype "bidirectional"))
      (node (ref "IC8") (pin "4") (pinfunction "IN_4") (pintype "bidirectional"))
    )
    (net (code "20") (name "/TX2") (class "Default")
      (node (ref "IC3") (pin "10") (pinfunction "IO15_10") (pintype "bidirectional"))
      (node (ref "IC4") (pin "12") (pinfunction "PA2_12") (pintype "bidirectional"))
      (node (ref "R28") (pin "1") (pinfunction "1_1") (pintype "passive"))
    )
    (net (code "21") (name "/Vcontrol") (class "Default")
      (node (ref "C1") (pin "2") (pinfunction "2_2") (pintype "passive"))
      (node (ref "IC1") (pin "1") (pinfunction "VSUP_1") (pintype "power_in"))
      (node (ref "IC1") (pin "16") (pinfunction "DVDD_16") (pintype "power_in"))
      (node (ref "Q1") (pin "2") (pinfunction "E_2") (pintype "bidirectional"))
      (node (ref "Q4") (pin "2") (pinfunction "S_2") (pintype "bidirectional"))
    )
    (net (code "22") (name "GND") (class "Default")
      (node (ref "1") (pin "2") (pinfunction "2_2") (pintype "bidirectional"))
      (node (ref "BOOT_0") (pin "3") (pinfunction "3_3") (pintype "power_in"))
      (node (ref "BOOT_1") (pin "3") (pinfunction "3_3") (pintype "power_in"))
      (node (ref "C1") (pin "1") (pinfunction "1_1") (pintype "passive"))
      (node (ref "C10") (pin "1") (pinfunction "1_1") (pintype "passive"))
      (node (ref "C11") (pin "1") (pinfunction "1_1") (pintype "passive"))
      (node (ref "C12") (pin "2") (pinfunction "2_2") (pintype "passive"))
      (node (ref "C13") (pin "2") (pinfunction "2_2") (pintype "passive"))
      (node (ref "C14") (pin "2") (pinfunction "2_2") (pintype "passive"))
      (node (ref "C15") (pin "1") (pinfunction "1_1") (pintype "passive"))
      (node (ref "C16") (pin "1") (pinfunction "1_1") (pintype "passive"))
      (node (ref "C17") (pin "2") (pinfunction "2_2") (pintype "passive"))
      (node (ref "C18") (pin "1") (pinfunction "1_1") (pintype "passive"))
      (node (ref "C19") (pin "1") (pinfunction "1_1") (pintype "passive"))
      (node (ref "C2") (pin "1") (pinfunction "1_1") (pintype "passive"))
      (node (ref "C20") (pin "1") (pinfunction "1_1") (pintype "passive"))
      (node (ref "C3") (pin "2") (pinfunction "2_2") (pintype "passive"))
      (node (ref "C6") (pin "2") (pinfunction "2_2") (pintype "passive"))
      (node (ref "C7") (pin "2") (pinfunction "2_2") (pintype "passive"))
      (node (ref "C8") (pin "1") (pinfunction "1_1") (pintype "passive"))
      (node (ref "C9") (pin "1") (pinfunction "1_1") (pintype "passive"))
      (node (ref "ESP Flash1") (pin "1") (pinfunction "1_1") (pintype "passive"))
      (node (ref "IC1") (pin "10") (pinfunction "INB+_10") (pintype "input"))
      (node (ref "IC1") (pin "14") (pinfunction "XI_14") (pintype "input"))
      (node (ref "IC1") (pin "15") (pinfunction "RATE_15") (pintype "input"))
      (node (ref "IC1") (pin "5") (pinfunction "AGND_5") (pintype "power_in"))
      (node (ref "IC1") (pin "9") (pinfunction "INB-_9") (pintype "input"))
      (node (ref "IC3") (pin "9") (pinfunction "GND_9") (pintype "bidirectional"))
      (node (ref "IC4") (pin "23") (pinfunction "VSS_1_23") (pintype "bidirectional"))
      (node (ref "IC4") (pin "35") (pinfunction "VSS_2_35") (pintype "bidirectional"))
      (node (ref "IC4") (pin "47") (pinfunction "VSS_3_47") (pintype "bidirectional"))
      (node (ref "IC4") (pin "8") (pinfunction "VSSA_8") (pintype "bidirectional"))
      (node (ref "IC5") (pin "2") (pinfunction "GND_2") (pintype "power_in"))
      (node (ref "IC6") (pin "2") (pinfunction "GND_1_2") (pintype "bidirectional"))
      (node (ref "IC7") (pin "2") (pinfunction "GND_1_2") (pintype "bidirectional"))
      (node (ref "IC8") (pin "2") (pinfunction "GND_1_2") (pintype "bidirectional"))
      (node (ref "LCD") (pin "4") (pinfunction "4_4") (pintype "bidirectional"))
      (node (ref "LED5") (pin "2") (pinfunction "2_2") (pintype "passive"))
      (node (ref "Q2") (pin "3") (pinfunction "S2_3") (pintype "bidirectional"))
      (node (ref "Q7") (pin "2") (pinfunction "S_2") (pintype "bidirectional"))
      (node (ref "R2") (pin "1") (pinfunction "1_1") (pintype "passive"))
      (node (ref "R20") (pin "2") (pinfunction "2_2") (pintype "passive"))
      (node (ref "R28") (pin "2") (pinfunction "2_2") (pintype "passive"))
      (node (ref "R36") (pin "2") (pinfunction "2_2") (pintype "passive"))
      (node (ref "R6") (pin "1") (pinfunction "1_1") (pintype "passive"))
      (node (ref "R8") (pin "1") (pinfunction "1_1") (pintype "passive"))
      (node (ref "Reset") (pin "2") (pinfunction "2_2") (pintype "bidirectional"))
      (node (ref "SWD1") (pin "1") (pinfunction "1_1") (pintype "power_in"))
      (node (ref "U1") (pin "2") (pinfunction "VSS_2") (pintype "power_in"))
      (node (ref "U3") (pin "1") (pinfunction "GND_1") (pintype "power_in"))
      (node (ref "U3") (pin "5") (pinfunction "SDO_5") (pintype "bidirectional"))
      (node (ref "USB1") (pin "5") (pinfunction "5_5") (pintype "bidirectional"))
      (node (ref "Weight_Sense") (pin "2") (pinfunction "2_2") (pintype "bidirectional"))
    )
    (net (code "23") (name "Net-(BOOT_0-COM)") (class "Default")
      (node (ref "BOOT_0") (pin "2") (pinfunction "COM_2") (pintype "bidirectional"))
      (node (ref "R10") (pin "2") (pinfunction "2_2") (pintype "passive"))
    )
    (net (code "24") (name "Net-(BOOT_1-COM)") (class "Default")
      (node (ref "BOOT_1") (pin "2") (pinfunction "COM_2") (pintype "bidirectional"))
      (node (ref "R26") (pin "1") (pinfunction "1_1") (pintype "passive"))
    )
    (net (code "25") (name "Net-(C6-Pad1)") (class "Default")
      (node (ref "C6") (pin "1") (pinfunction "1_1") (pintype "passive"))
      (node (ref "USB1") (pin "2") (pinfunction "2_2") (pintype "bidirectional"))
      (node (ref "USB1") (pin "3") (pinfunction "3_3") (pintype "bidirectional"))
      (node (ref "USB1") (pin "4") (pinfunction "4_4") (pintype "bidirectional"))
    )
    (net (code "26") (name "Net-(C15-Pad2)") (class "Default")
      (node (ref "C15") (pin "2") (pinfunction "2_2") (pintype "passive"))
      (node (ref "R16") (pin "2") (pinfunction "2_2") (pintype "passive"))
      (node (ref "Y1") (pin "2") (pinfunction "2_2") (pintype "bidirectional"))
    )
    (net (code "27") (name "Net-(C16-Pad2)") (class "Default")
      (node (ref "C16") (pin "2") (pinfunction "2_2") (pintype "passive"))
      (node (ref "R15") (pin "1") (pinfunction "1_1") (pintype "passive"))
      (node (ref "Reset") (pin "1") (pinfunction "1_1") (pintype "bidirectional"))
    )
    (net (code "28") (name "Net-(D1-K)") (class "Default")
      (node (ref "D1") (pin "3") (pinfunction "K_3") (pintype "passive"))
      (node (ref "U1") (pin "4") (pinfunction "VDD_4") (pintype "power_in"))
    )
    (net (code "29") (name "Net-(D2-K)") (class "Default")
      (node (ref "C11") (pin "2") (pinfunction "2_2") (pintype "passive"))
      (node (ref "D2") (pin "1") (pinfunction "K_1") (pintype "bidirectional"))
      (node (ref "IC5") (pin "1") (pinfunction "VIN_1") (pintype "power_in"))
      (node (ref "IC5") (pin "3") (pinfunction "!SHDN_3") (pintype "bidirectional"))
      (node (ref "Q3") (pin "3") (pinfunction "D_3") (pintype "bidirectional"))
    )
    (net (code "30") (name "Net-(IC1-BASE)") (class "Default")
      (node (ref "IC1") (pin "2") (pinfunction "BASE_2") (pintype "output"))
      (node (ref "Q1") (pin "1") (pinfunction "B_1") (pintype "bidirectional"))
    )
    (net (code "31") (name "Net-(IC1-INA+)") (class "Default")
      (node (ref "C4") (pin "1") (pinfunction "1_1") (pintype "passive"))
      (node (ref "IC1") (pin "8") (pinfunction "INA+_8") (pintype "input"))
      (node (ref "R4") (pin "1") (pinfunction "1_1") (pintype "passive"))
    )
    (net (code "32") (name "Net-(IC1-INA-)") (class "Default")
      (node (ref "C4") (pin "2") (pinfunction "2_2") (pintype "passive"))
      (node (ref "IC1") (pin "7") (pinfunction "INA-_7") (pintype "input"))
      (node (ref "R3") (pin "1") (pinfunction "1_1") (pintype "passive"))
    )
    (net (code "33") (name "Net-(IC1-VBG)") (class "Default")
      (node (ref "C3") (pin "1") (pinfunction "1_1") (pintype "passive"))
      (node (ref "IC1") (pin "6") (pinfunction "VBG_6") (pintype "output"))
    )
    (net (code "34") (name "Net-(IC1-VFB)") (class "Default")
      (node (ref "IC1") (pin "4") (pinfunction "VFB_4") (pintype "input"))
      (node (ref "R1") (pin "1") (pinfunction "1_1") (pintype "passive"))
      (node (ref "R2") (pin "2") (pinfunction "2_2") (pintype "passive"))
    )
    (net (code "35") (name "Net-(IC2-CS)") (class "Default")
      (node (ref "IC2") (pin "2") (pinfunction "CS_2") (pintype "bidirectional"))
      (node (ref "R8") (pin "2") (pinfunction "2_2") (pintype "passive"))
    )
    (net (code "36") (name "Net-(IC2-GND)") (class "Default")
      (node (ref "BT1") (pin "-") (pinfunction "-_-") (pintype "passive"))
      (node (ref "C5") (pin "1") (pinfunction "1_1") (pintype "passive"))
      (node (ref "IC2") (pin "6") (pinfunction "GND_6") (pintype "power_in"))
      (node (ref "Q2") (pin "1") (pinfunction "S1_1") (pintype "bidirectional"))
    )
    (net (code "37") (name "Net-(IC2-OC)") (class "Default")
      (node (ref "IC2") (pin "3") (pinfunction "OC_3") (pintype "bidirectional"))
      (node (ref "Q2") (pin "4") (pinfunction "G2_4") (pintype "bidirectional"))
    )
    (net (code "38") (name "Net-(IC2-OD)") (class "Default")
      (node (ref "IC2") (pin "1") (pinfunction "OD_1") (pintype "bidirectional"))
      (node (ref "Q2") (pin "6") (pinfunction "G1_6") (pintype "bidirectional"))
    )
    (net (code "39") (name "Net-(IC2-VCC)") (class "Default")
      (node (ref "C5") (pin "2") (pinfunction "2_2") (pintype "passive"))
      (node (ref "IC2") (pin "5") (pinfunction "VCC_5") (pintype "power_in"))
      (node (ref "R7") (pin "2") (pinfunction "2_2") (pintype "passive"))
    )
    (net (code "40") (name "Net-(IC3-EN)") (class "Default")
      (node (ref "IC3") (pin "3") (pinfunction "EN_3") (pintype "bidirectional"))
      (node (ref "R19") (pin "2") (pinfunction "2_2") (pintype "passive"))
    )
    (net (code "41") (name "Net-(IC3-IO2)") (class "Default")
      (node (ref "IC3") (pin "11") (pinfunction "IO2_11") (pintype "bidirectional"))
      (node (ref "R27") (pin "2") (pinfunction "2_2") (pintype "passive"))
    )
    (net (code "42") (name "Net-(IC4-BOOT0)") (class "Default")
      (node (ref "IC4") (pin "44") (pinfunction "BOOT0_44") (pintype "bidirectional"))
      (node (ref "R10") (pin "1") (pinfunction "1_1") (pintype "passive"))
    )
    (net (code "43") (name "Net-(IC4-PA8)") (class "Default")
      (node (ref "IC4") (pin "29") (pinfunction "PA8_29") (pintype "bidirectional"))
      (node (ref "R18") (pin "2") (pinfunction "2_2") (pintype "passive"))
    )
    (net (code "44") (name "Net-(IC4-PB2)") (class "Default")
      (node (ref "IC4") (pin "20") (pinfunction "PB2_20") (pintype "bidirectional"))
      (node (ref "R26") (pin "2") (pinfunction "2_2") (pintype "passive"))
    )
    (net (code "45") (name "Net-(IC4-PC14-OSC32_IN)") (class "Default")
      (node (ref "C12") (pin "1") (pinfunction "1_1") (pintype "passive"))
      (node (ref "IC4") (pin "3") (pinfunction "PC14-OSC32_IN_3") (pintype "bidirectional"))
      (node (ref "Y1") (pin "1") (pinfunction "1_1") (pintype "bidirectional"))
    )
    (net (code "46") (name "Net-(IC4-PC15-OSC32_OUT)") (class "Default")
      (node (ref "IC4") (pin "4") (pinfunction "PC15-OSC32_OUT_4") (pintype "bidirectional"))
      (node (ref "R16") (pin "1") (pinfunction "1_1") (pintype "passive"))
    )
    (net (code "47") (name "Net-(IC5-LX)") (class "Default")
      (node (ref "IC5") (pin "5") (pinfunction "LX_5") (pintype "bidirectional"))
      (node (ref "L1") (pin "2") (pinfunction "2_2") (pintype "passive"))
    )
    (net (code "48") (name "Net-(IC6-OUT1)") (class "Default")
      (node (ref "IC6") (pin "1") (pinfunction "OUT1_1") (pintype "bidirectional"))
      (node (ref "R17") (pin "1") (pinfunction "1_1") (pintype "passive"))
    )
    (net (code "49") (name "Net-(IC7-OUT1)") (class "Default")
      (node (ref "IC7") (pin "1") (pinfunction "OUT1_1") (pintype "bidirectional"))
      (node (ref "R24") (pin "1") (pinfunction "1_1") (pintype "passive"))
    )
    (net (code "50") (name "Net-(IC8-OUT1)") (class "Default")
      (node (ref "IC8") (pin "1") (pinfunction "OUT1_1") (pintype "bidirectional"))
      (node (ref "R25") (pin "1") (pinfunction "1_1") (pintype "passive"))
    )
    (net (code "51") (name "Net-(LED1-Pad1)") (class "Default")
      (node (ref "LED1") (pin "1") (pinfunction "1_1") (pintype "passive"))
      (node (ref "R25") (pin "2") (pinfunction "2_2") (pintype "passive"))
    )
    (net (code "52") (name "Net-(LED2-Pad1)") (class "Default")
      (node (ref "LED2") (pin "1") (pinfunction "1_1") (pintype "passive"))
      (node (ref "R24") (pin "2") (pinfunction "2_2") (pintype "passive"))
    )
    (net (code "53") (name "Net-(LED3-Pad1)") (class "Default")
      (node (ref "LED3") (pin "1") (pinfunction "1_1") (pintype "passive"))
      (node (ref "R17") (pin "2") (pinfunction "2_2") (pintype "passive"))
    )
    (net (code "54") (name "Net-(LED4-Pad1)") (class "Default")
      (node (ref "LED4") (pin "1") (pinfunction "1_1") (pintype "passive"))
      (node (ref "R30") (pin "2") (pinfunction "2_2") (pintype "passive"))
    )
    (net (code "55") (name "Net-(LED5-Pad1)") (class "Default")
      (node (ref "LED5") (pin "1") (pinfunction "1_1") (pintype "passive"))
      (node (ref "R12") (pin "2") (pinfunction "2_2") (pintype "passive"))
    )
    (net (code "56") (name "Net-(LED6-Pad2)") (class "Default")
      (node (ref "LED6") (pin "2") (pinfunction "2_2") (pintype "passive"))
      (node (ref "R5") (pin "2") (pinfunction "2_2") (pintype "passive"))
    )
    (net (code "57") (name "Net-(Q4-G)") (class "Default")
      (node (ref "Q4") (pin "1") (pinfunction "G_1") (pintype "bidirectional"))
      (node (ref "R18") (pin "1") (pinfunction "1_1") (pintype "passive"))
      (node (ref "R20") (pin "1") (pinfunction "1_1") (pintype "passive"))
    )
    (net (code "58") (name "Net-(Q7-D)") (class "Default")
      (node (ref "LED4") (pin "2") (pinfunction "2_2") (pintype "passive"))
      (node (ref "Q7") (pin "3") (pinfunction "D_3") (pintype "bidirectional"))
    )
    (net (code "59") (name "Net-(Q7-G)") (class "Default")
      (node (ref "Q7") (pin "1") (pinfunction "G_1") (pintype "bidirectional"))
      (node (ref "R33") (pin "1") (pinfunction "1_1") (pintype "passive"))
      (node (ref "R36") (pin "1") (pinfunction "1_1") (pintype "passive"))
    )
    (net (code "60") (name "Net-(U1-PROG)") (class "Default")
      (node (ref "R6") (pin "2") (pinfunction "2_2") (pintype "passive"))
      (node (ref "U1") (pin "5") (pinfunction "PROG_5") (pintype "input"))
    )
    (net (code "61") (name "Net-(U1-STAT)") (class "Default")
      (node (ref "LED6") (pin "1") (pinfunction "1_1") (pintype "passive"))
      (node (ref "U1") (pin "1") (pinfunction "STAT_1") (pintype "input"))
    )
    (net (code "62") (name "Vbat") (class "Default")
      (node (ref "BT1") (pin "+") (pinfunction "+_+") (pintype "passive"))
      (node (ref "Q3") (pin "2") (pinfunction "S_2") (pintype "bidirectional"))
      (node (ref "R7") (pin "1") (pinfunction "1_1") (pintype "passive"))
      (node (ref "U1") (pin "3") (pinfunction "VBAT_3") (pintype "power_in"))
    )
    (net (code "63") (name "unconnected-(IC1-XO-Pad13)") (class "Default")
      (node (ref "IC1") (pin "13") (pinfunction "XO_13") (pintype "bidirectional+no_connect"))
    )
    (net (code "64") (name "unconnected-(IC2-TD-Pad4)") (class "Default")
      (node (ref "IC2") (pin "4") (pinfunction "TD_4") (pintype "bidirectional"))
    )
    (net (code "65") (name "unconnected-(IC3-ADC-Pad2)") (class "Default")
      (node (ref "IC3") (pin "2") (pinfunction "ADC_2") (pintype "bidirectional"))
    )
    (net (code "66") (name "unconnected-(IC3-IO4-Pad13)") (class "Default")
      (node (ref "IC3") (pin "13") (pinfunction "IO4_13") (pintype "bidirectional"))
    )
    (net (code "67") (name "unconnected-(IC3-IO5-Pad14)") (class "Default")
      (node (ref "IC3") (pin "14") (pinfunction "IO5_14") (pintype "bidirectional"))
    )
    (net (code "68") (name "unconnected-(IC3-IO12-Pad6)") (class "Default")
      (node (ref "IC3") (pin "6") (pinfunction "IO12_6") (pintype "bidirectional"))
    )
    (net (code "69") (name "unconnected-(IC3-IO14-Pad5)") (class "Default")
      (node (ref "IC3") (pin "5") (pinfunction "IO14_5") (pintype "bidirectional"))
    )
    (net (code "70") (name "unconnected-(IC3-IO16-Pad4)") (class "Default")
      (node (ref "IC3") (pin "4") (pinfunction "IO16_4") (pintype "bidirectional"))
    )
    (net (code "71") (name "unconnected-(IC4-PA0-WKUP-Pad10)") (class "Default")
      (node (ref "IC4") (pin "10") (pinfunction "PA0-WKUP_10") (pintype "bidirectional"))
    )
    (net (code "72") (name "unconnected-(IC4-PA1-Pad11)") (class "Default")
      (node (ref "IC4") (pin "11") (pinfunction "PA1_11") (pintype "bidirectional"))
    )
    (net (code "73") (name "unconnected-(IC4-PA4-Pad14)") (class "Default")
      (node (ref "IC4") (pin "14") (pinfunction "PA4_14") (pintype "bidirectional"))
    )
    (net (code "74") (name "unconnected-(IC4-PA5-Pad15)") (class "Default")
      (node (ref "IC4") (pin "15") (pinfunction "PA5_15") (pintype "bidirectional"))
    )
    (net (code "75") (name "unconnected-(IC4-PA6-Pad16)") (class "Default")
      (node (ref "IC4") (pin "16") (pinfunction "PA6_16") (pintype "bidirectional"))
    )
    (net (code "76") (name "unconnected-(IC4-PA7-Pad17)") (class "Default")
      (node (ref "IC4") (pin "17") (pinfunction "PA7_17") (pintype "bidirectional"))
    )
    (net (code "77") (name "unconnected-(IC4-PA11-Pad32)") (class "Default")
      (node (ref "IC4") (pin "32") (pinfunction "PA11_32") (pintype "bidirectional"))
    )
    (net (code "78") (name "unconnected-(IC4-PA12-Pad33)") (class "Default")
      (node (ref "IC4") (pin "33") (pinfunction "PA12_33") (pintype "bidirectional"))
    )
    (net (code "79") (name "unconnected-(IC4-PA15-Pad38)") (class "Default")
      (node (ref "IC4") (pin "38") (pinfunction "PA15_38") (pintype "bidirectional+no_connect"))
    )
    (net (code "80") (name "unconnected-(IC4-PB0-Pad18)") (class "Default")
      (node (ref "IC4") (pin "18") (pinfunction "PB0_18") (pintype "bidirectional"))
    )
    (net (code "81") (name "unconnected-(IC4-PB1-Pad19)") (class "Default")
      (node (ref "IC4") (pin "19") (pinfunction "PB1_19") (pintype "bidirectional"))
    )
    (net (code "82") (name "unconnected-(IC4-PB3-Pad39)") (class "Default")
      (node (ref "IC4") (pin "39") (pinfunction "PB3_39") (pintype "bidirectional+no_connect"))
    )
    (net (code "83") (name "unconnected-(IC4-PB4-Pad40)") (class "Default")
      (node (ref "IC4") (pin "40") (pinfunction "PB4_40") (pintype "bidirectional"))
    )
    (net (code "84") (name "unconnected-(IC4-PB5-Pad41)") (class "Default")
      (node (ref "IC4") (pin "41") (pinfunction "PB5_41") (pintype "bidirectional"))
    )
    (net (code "85") (name "unconnected-(IC4-PB8-Pad45)") (class "Default")
      (node (ref "IC4") (pin "45") (pinfunction "PB8_45") (pintype "bidirectional"))
    )
    (net (code "86") (name "unconnected-(IC4-PB9-Pad46)") (class "Default")
      (node (ref "IC4") (pin "46") (pinfunction "PB9_46") (pintype "bidirectional"))
    )
    (net (code "87") (name "unconnected-(IC4-PB12-Pad25)") (class "Default")
      (node (ref "IC4") (pin "25") (pinfunction "PB12_25") (pintype "bidirectional"))
    )
    (net (code "88") (name "unconnected-(IC4-PB13-Pad26)") (class "Default")
      (node (ref "IC4") (pin "26") (pinfunction "PB13_26") (pintype "bidirectional"))
    )
    (net (code "89") (name "unconnected-(IC4-PC13-TAMPER-RTC-Pad2)") (class "Default")
      (node (ref "IC4") (pin "2") (pinfunction "PC13-TAMPER-RTC_2") (pintype "bidirectional"))
    )
    (net (code "90") (name "unconnected-(IC4-PD0-OSC_IN-Pad5)") (class "Default")
      (node (ref "IC4") (pin "5") (pinfunction "PD0-OSC_IN_5") (pintype "bidirectional"))
    )
    (net (code "91") (name "unconnected-(IC4-PD1-OSC_OUT-Pad6)") (class "Default")
      (node (ref "IC4") (pin "6") (pinfunction "PD1-OSC_OUT_6") (pintype "bidirectional"))
    )
    (net (code "92") (name "unconnected-(IC6-GND_2-Pad5)") (class "Default")
      (node (ref "IC6") (pin "5") (pinfunction "GND_2_5") (pintype "bidirectional"))
    )
    (net (code "93") (name "unconnected-(IC6-OUT2-Pad3)") (class "Default")
      (node (ref "IC6") (pin "3") (pinfunction "OUT2_3") (pintype "bidirectional"))
    )
    (net (code "94") (name "unconnected-(IC7-GND_2-Pad5)") (class "Default")
      (node (ref "IC7") (pin "5") (pinfunction "GND_2_5") (pintype "bidirectional"))
    )
    (net (code "95") (name "unconnected-(IC7-OUT2-Pad3)") (class "Default")
      (node (ref "IC7") (pin "3") (pinfunction "OUT2_3") (pintype "bidirectional"))
    )
    (net (code "96") (name "unconnected-(IC8-GND_2-Pad5)") (class "Default")
      (node (ref "IC8") (pin "5") (pinfunction "GND_2_5") (pintype "bidirectional"))
    )
    (net (code "97") (name "unconnected-(IC8-OUT2-Pad3)") (class "Default")
      (node (ref "IC8") (pin "3") (pinfunction "OUT2_3") (pintype "bidirectional"))
    )
    (net (code "98") (name "unconnected-(Q2-1{slash}D2-Pad2)") (class "Default")
      (node (ref "Q2") (pin "2") (pinfunction "1/D2_2") (pintype "bidirectional+no_connect"))
    )
    (net (code "99") (name "unconnected-(Q2-D1{slash}D2-Pad5)") (class "Default")
      (node (ref "Q2") (pin "5") (pinfunction "D1/D2_5") (pintype "bidirectional+no_connect"))
    )
    (net (code "100") (name "unconnected-(Reset-Pad3)") (class "Default")
      (node (ref "Reset") (pin "3") (pinfunction "3_3") (pintype "bidirectional+no_connect"))
    )
    (net (code "101") (name "unconnected-(Reset-Pad4)") (class "Default")
      (node (ref "Reset") (pin "4") (pinfunction "4_4") (pintype "bidirectional+no_connect"))
    )
    (net (code "102") (name "unconnected-(SWD1-Pad2)") (class "Default")
      (node (ref "SWD1") (pin "2") (pinfunction "2_2") (pintype "passive+no_connect"))
    )
    (net (code "103") (name "unconnected-(SWD1-Pad3)") (class "Default")
      (node (ref "SWD1") (pin "3") (pinfunction "3_3") (pintype "passive+no_connect"))
    )
    (net (code "104") (name "unconnected-(SWD1-Pad4)") (class "Default")
      (node (ref "SWD1") (pin "4") (pinfunction "4_4") (pintype "passive+no_connect"))
    )
    (net (code "105") (name "unconnected-(USB1-PadMH1)") (class "Default")
      (node (ref "USB1") (pin "MH1") (pinfunction "MH1_MH1") (pintype "bidirectional+no_connect"))
    )
    (net (code "106") (name "unconnected-(USB1-PadMH2)") (class "Default")
      (node (ref "USB1") (pin "MH2") (pinfunction "MH2_MH2") (pintype "bidirectional+no_connect"))
    )
    (net (code "107") (name "unconnected-(USB1-PadMH3)") (class "Default")
      (node (ref "USB1") (pin "MH3") (pinfunction "MH3_MH3") (pintype "bidirectional+no_connect"))
    )
    (net (code "108") (name "unconnected-(USB1-PadMH4)") (class "Default")
      (node (ref "USB1") (pin "MH4") (pinfunction "MH4_MH4") (pintype "bidirectional+no_connect"))
    )
    (net (code "109") (name "unconnected-(USB1-PadMP1)") (class "Default")
      (node (ref "USB1") (pin "MP1") (pinfunction "MP1_MP1") (pintype "bidirectional+no_connect"))
    )
    (net (code "110") (name "unconnected-(USB1-PadMP2)") (class "Default")
      (node (ref "USB1") (pin "MP2") (pinfunction "MP2_MP2") (pintype "bidirectional+no_connect"))
    )
  )
)
